# v1_0.net
KiCad netlist of a schematic drawn in EAGLE
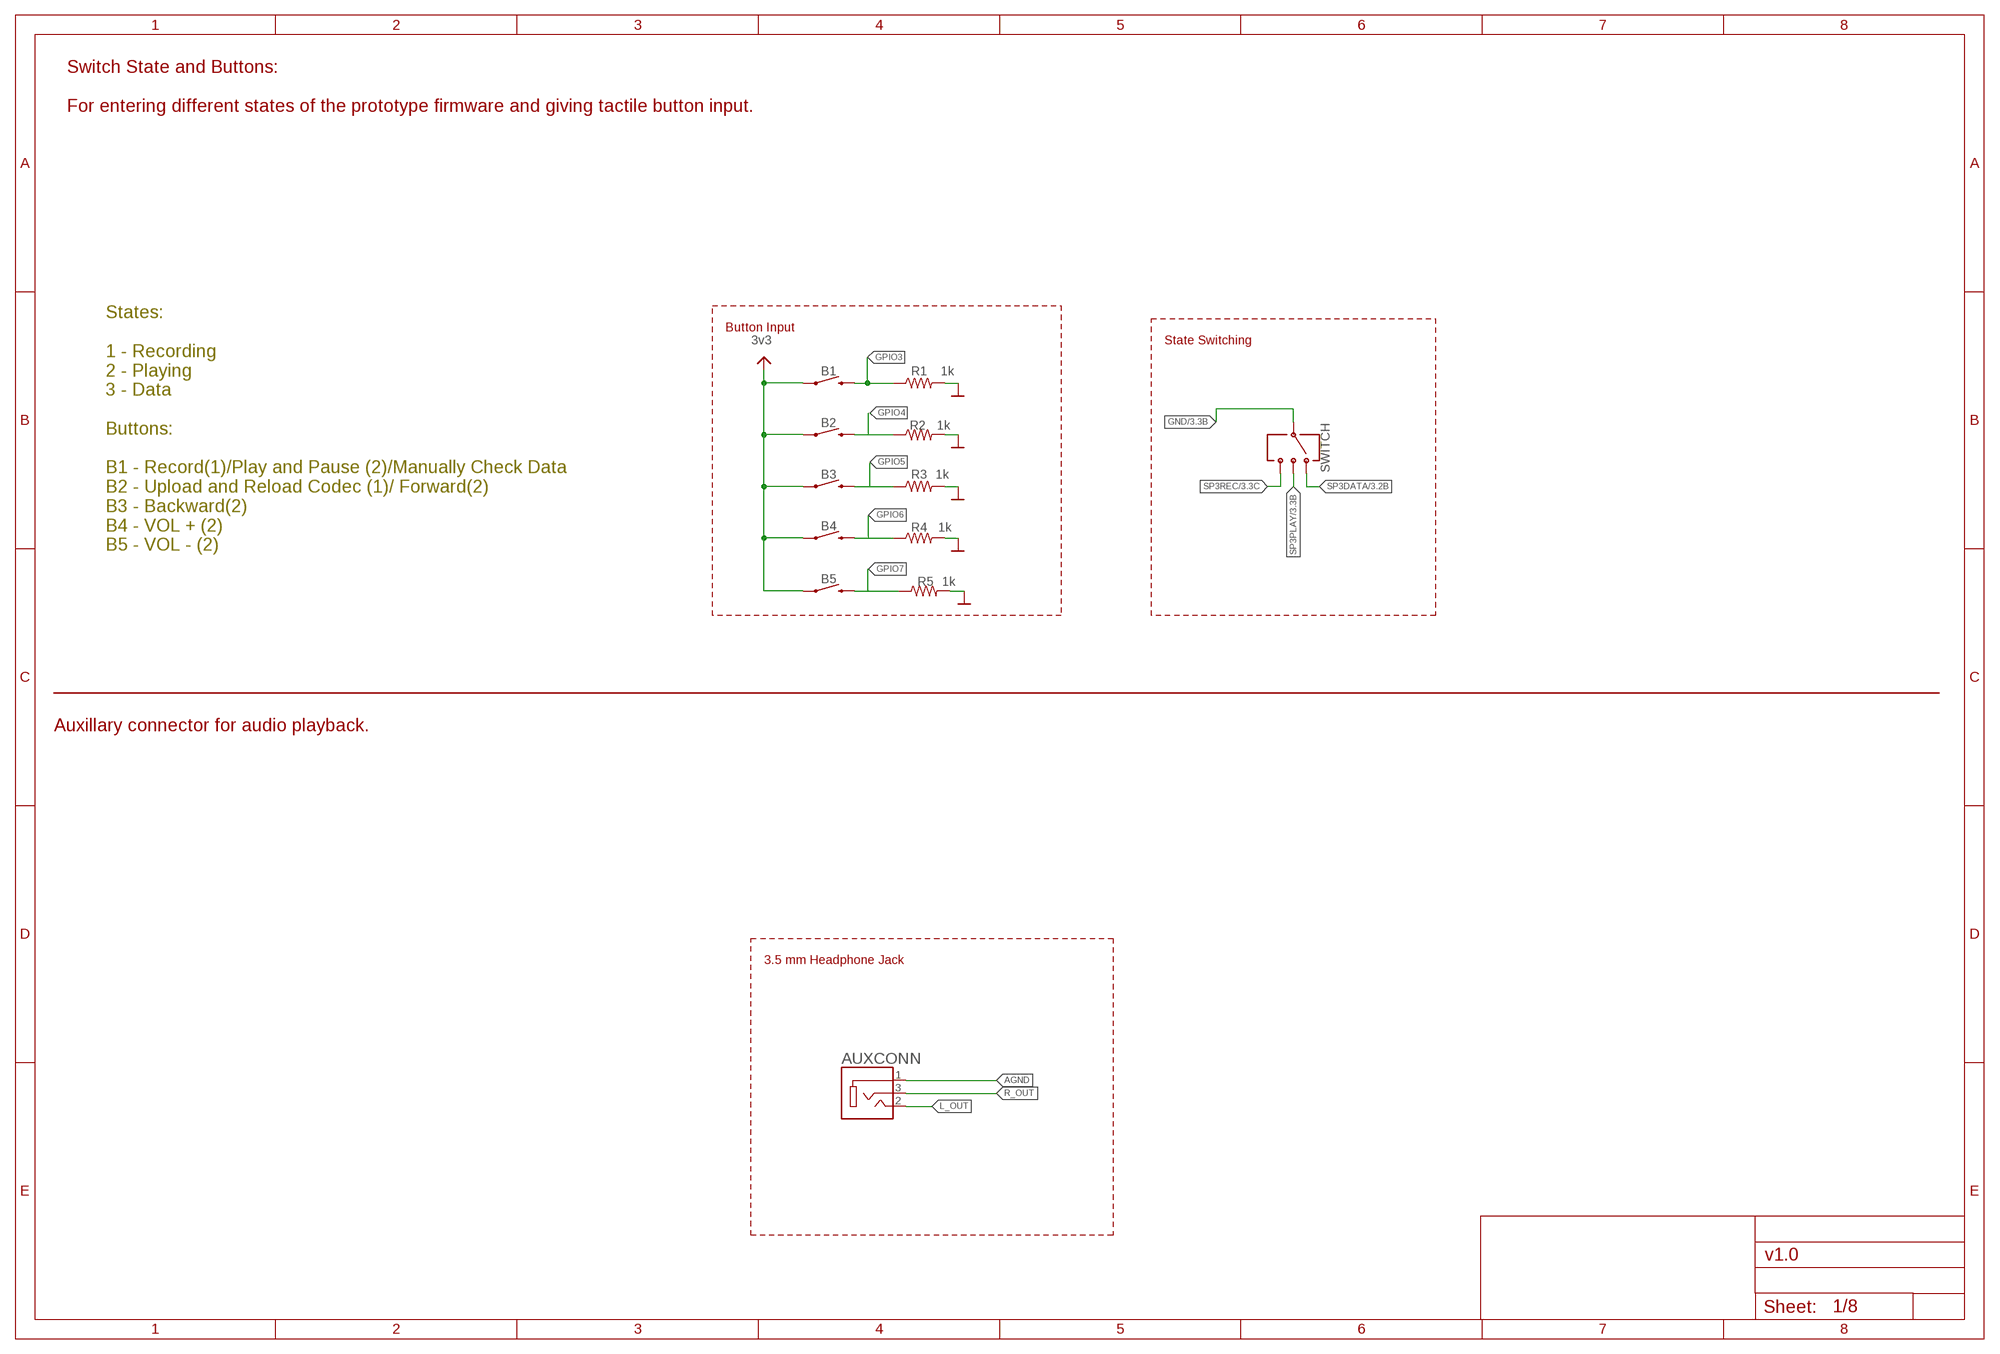
[diagram p0: schematic, sheet 1]
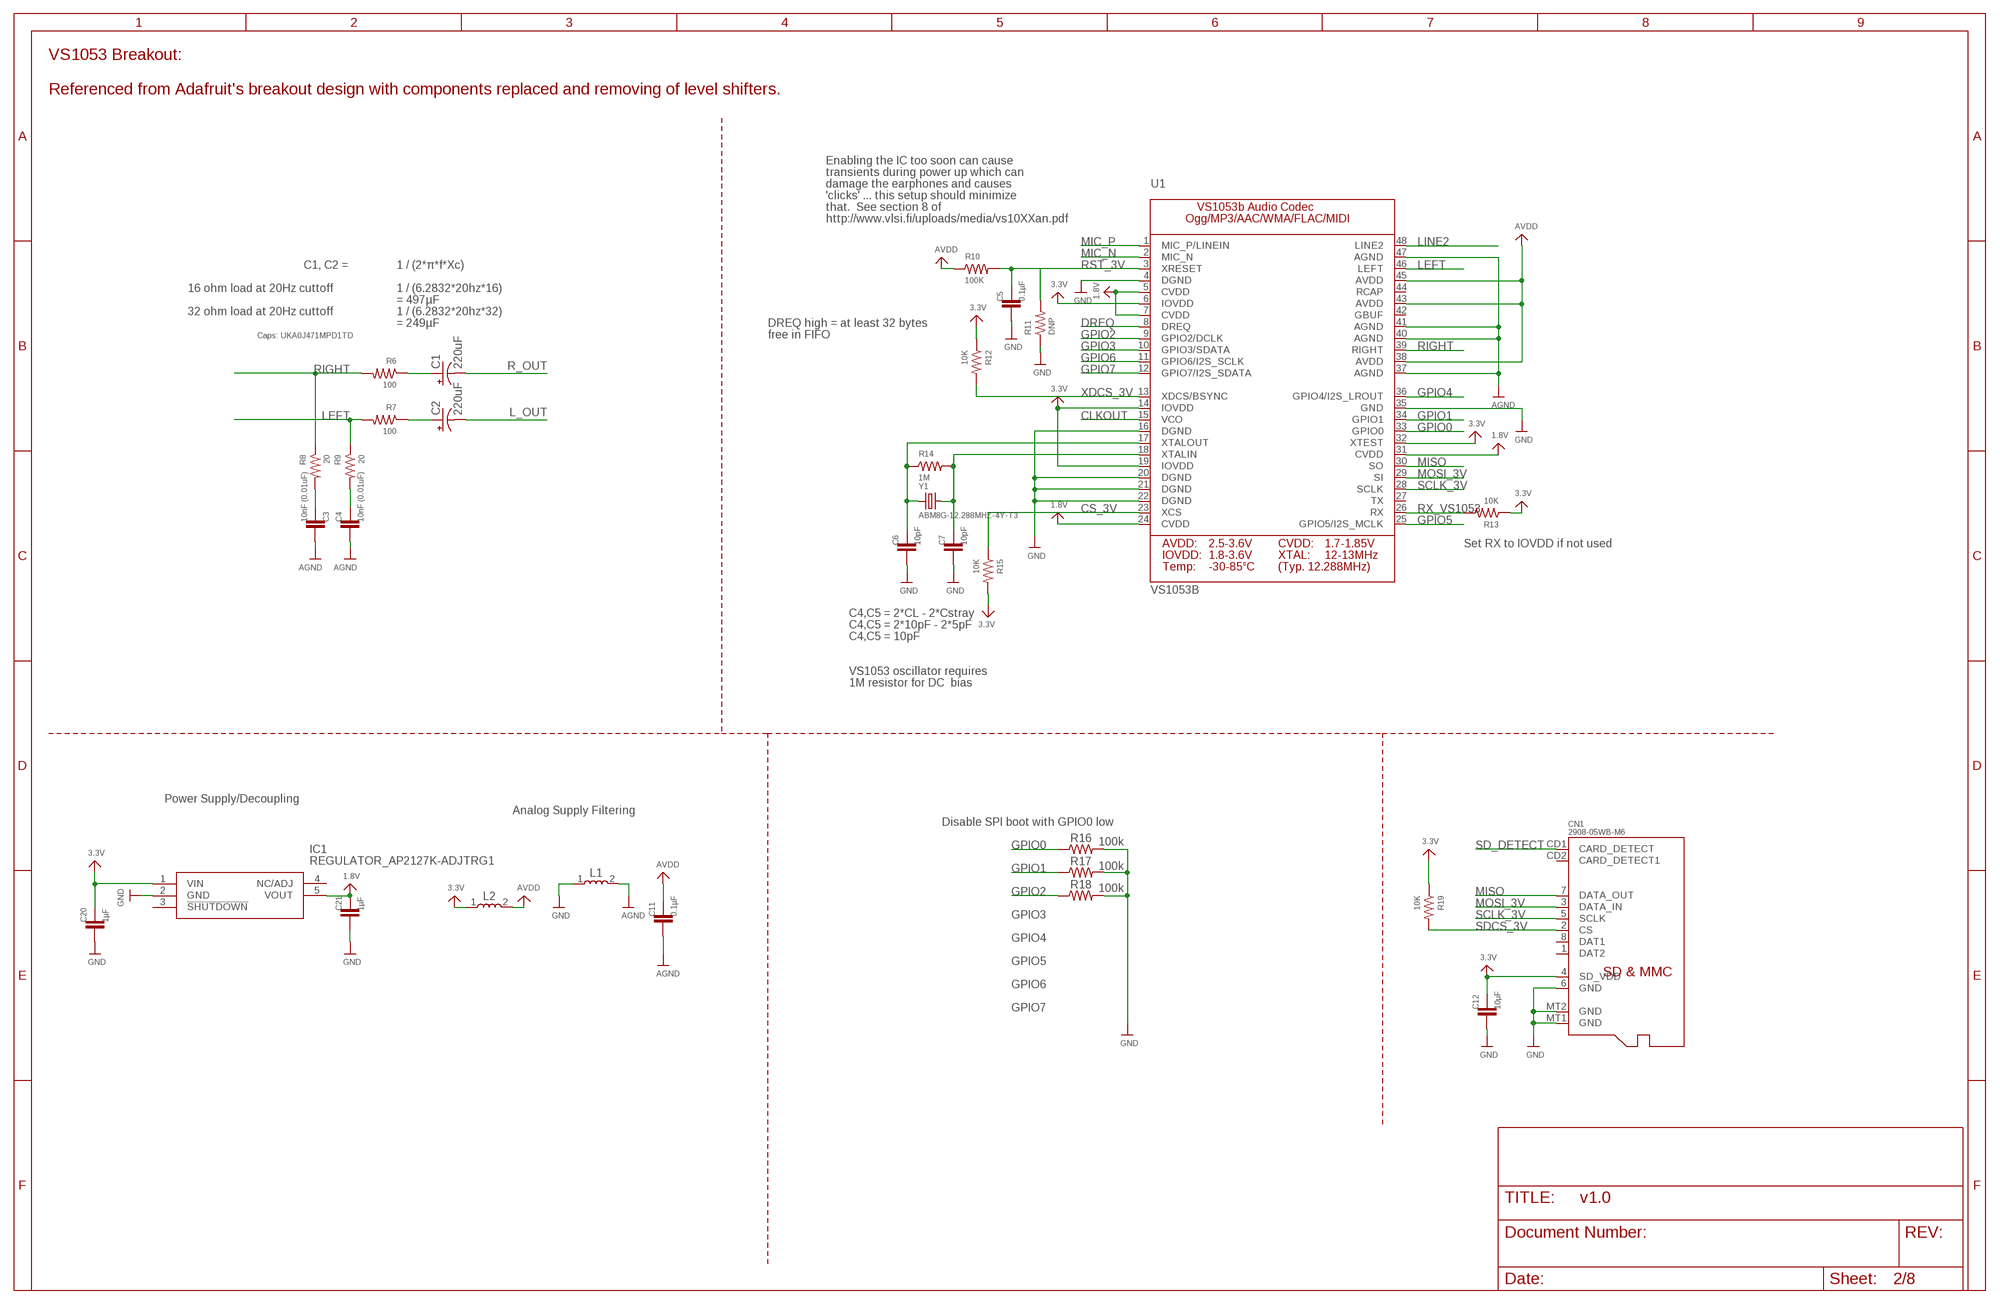
[diagram p1: schematic, sheet 2]
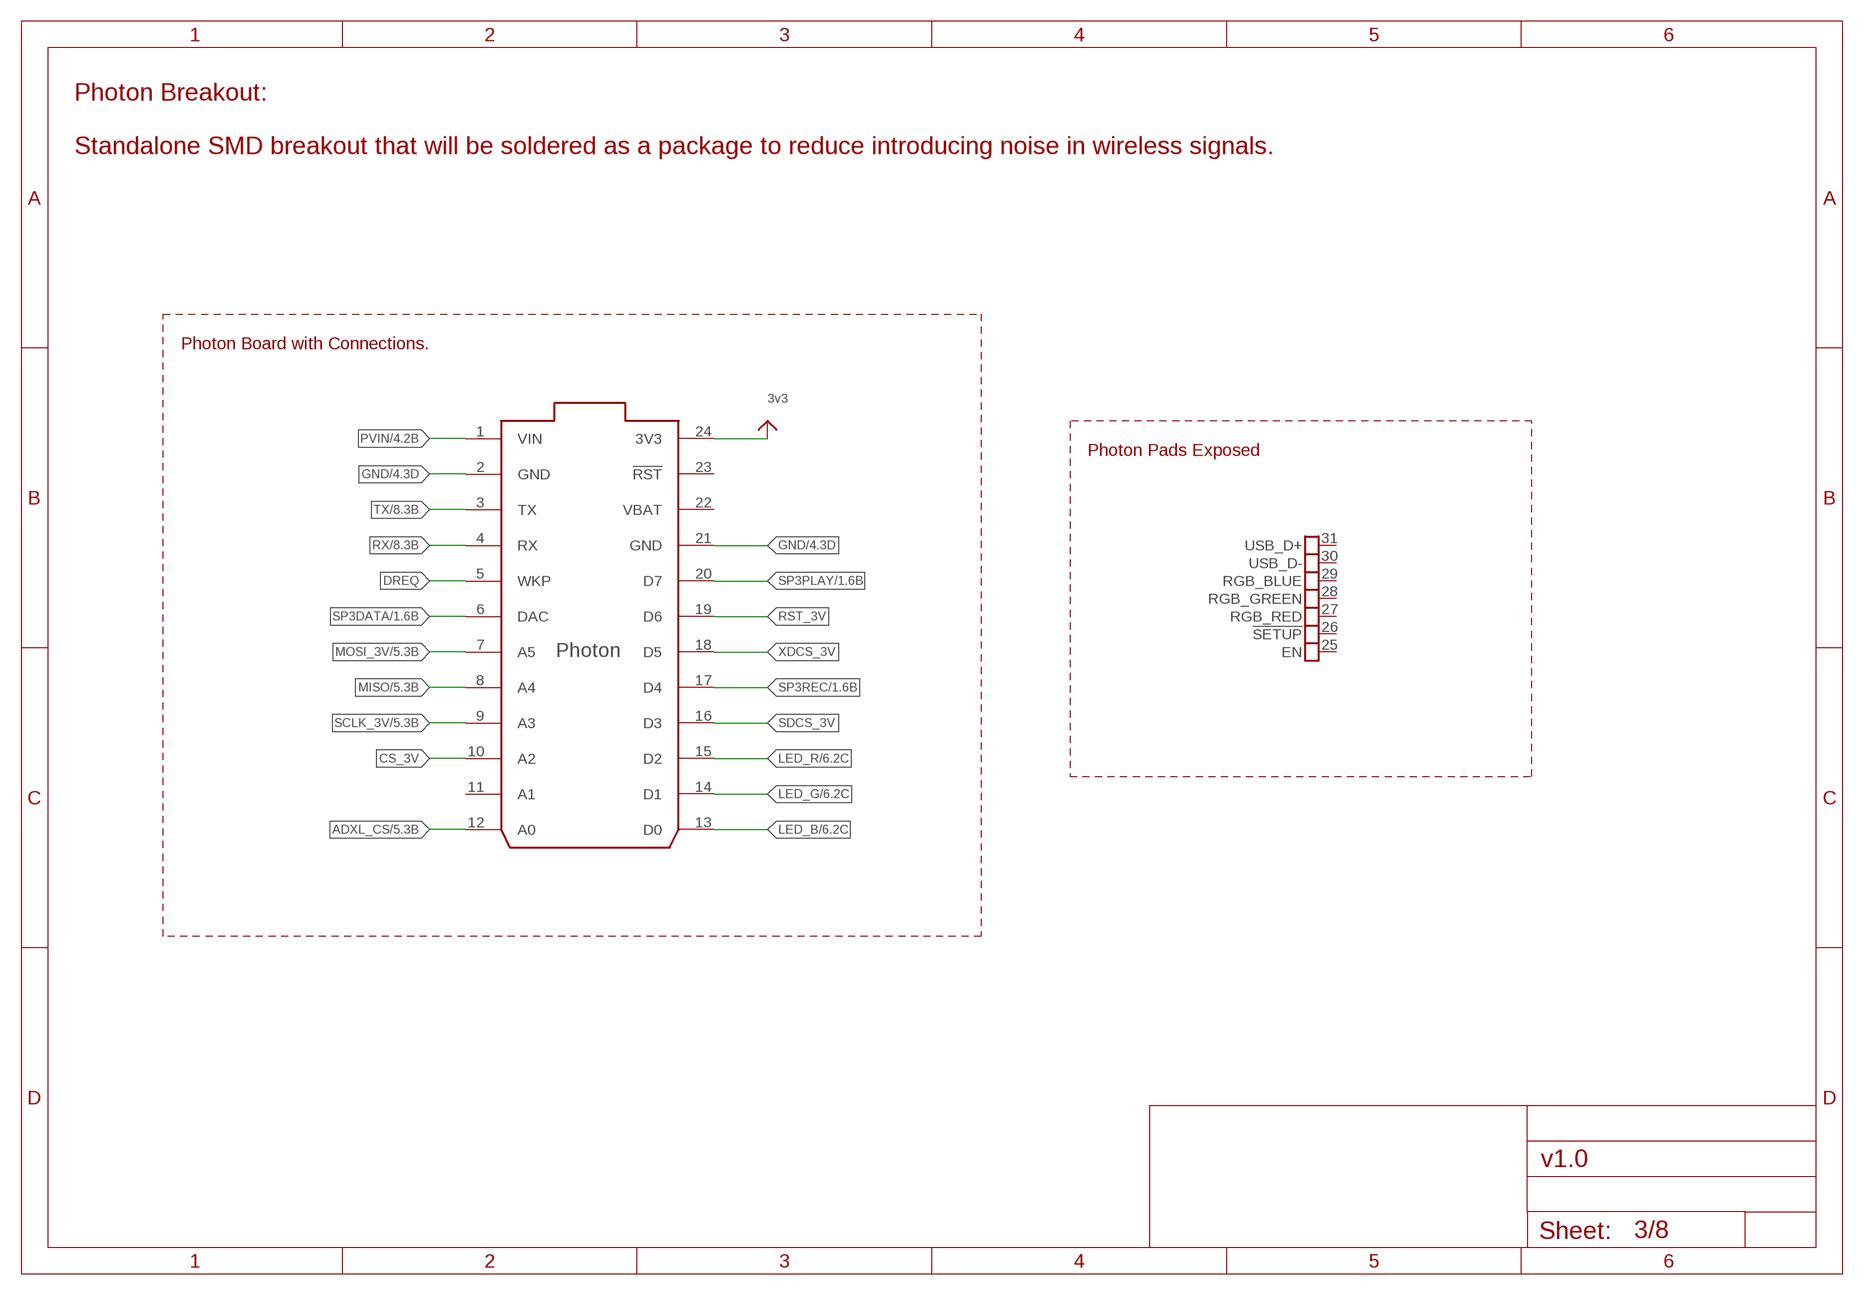
[diagram p2: schematic, sheet 3]
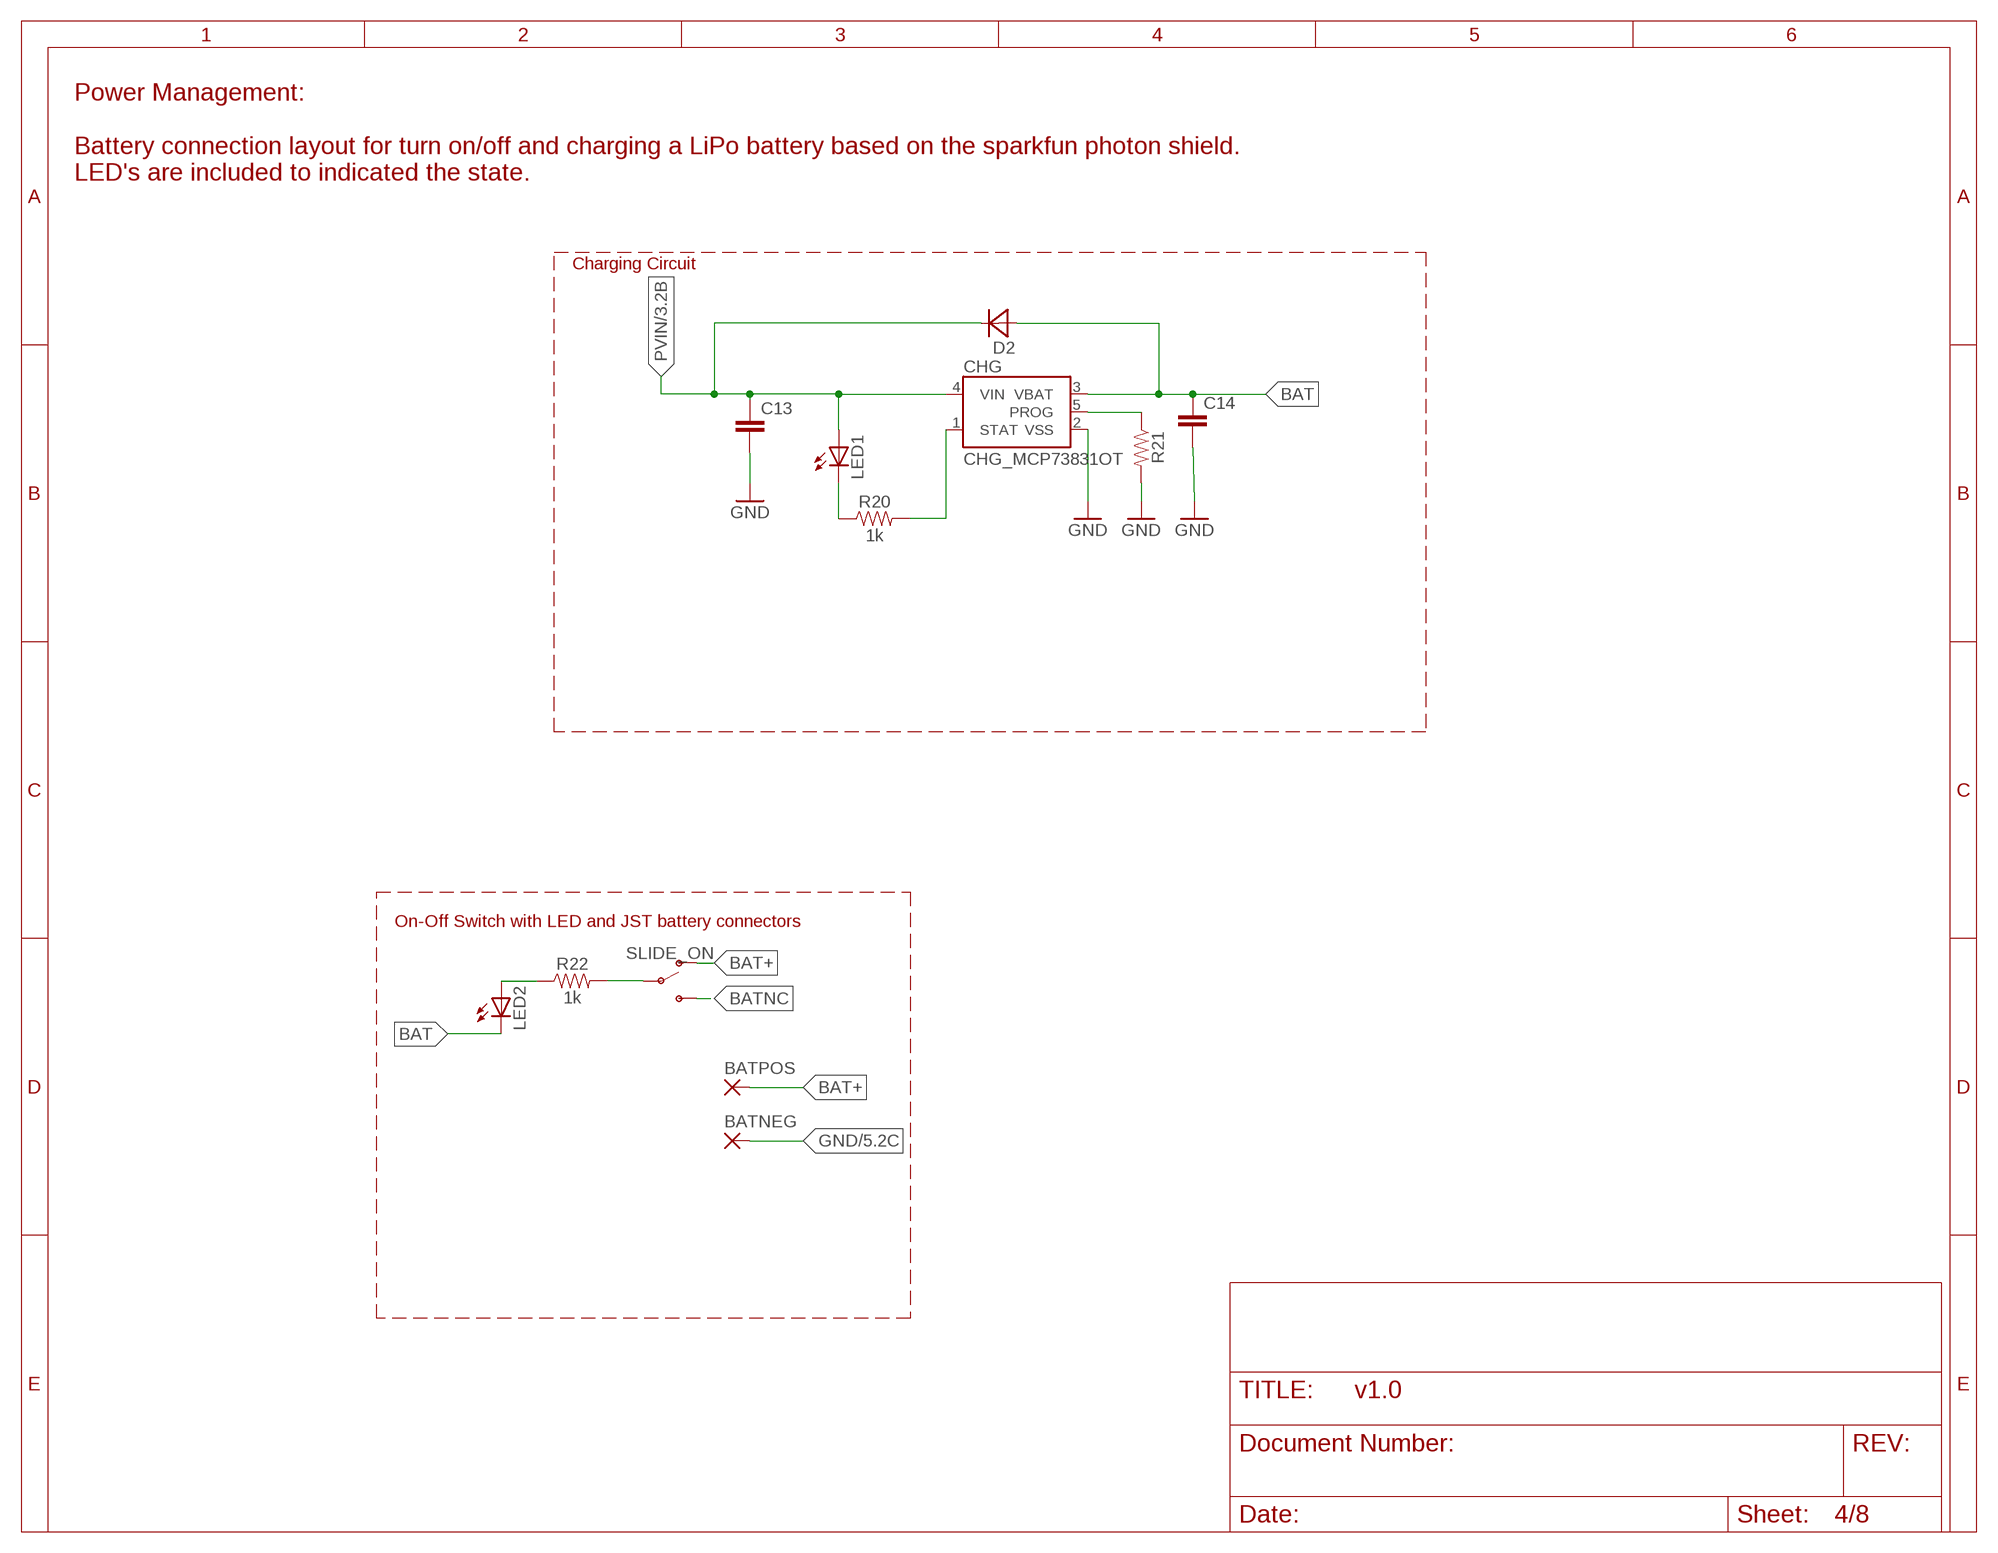
[diagram p3: schematic, sheet 4]
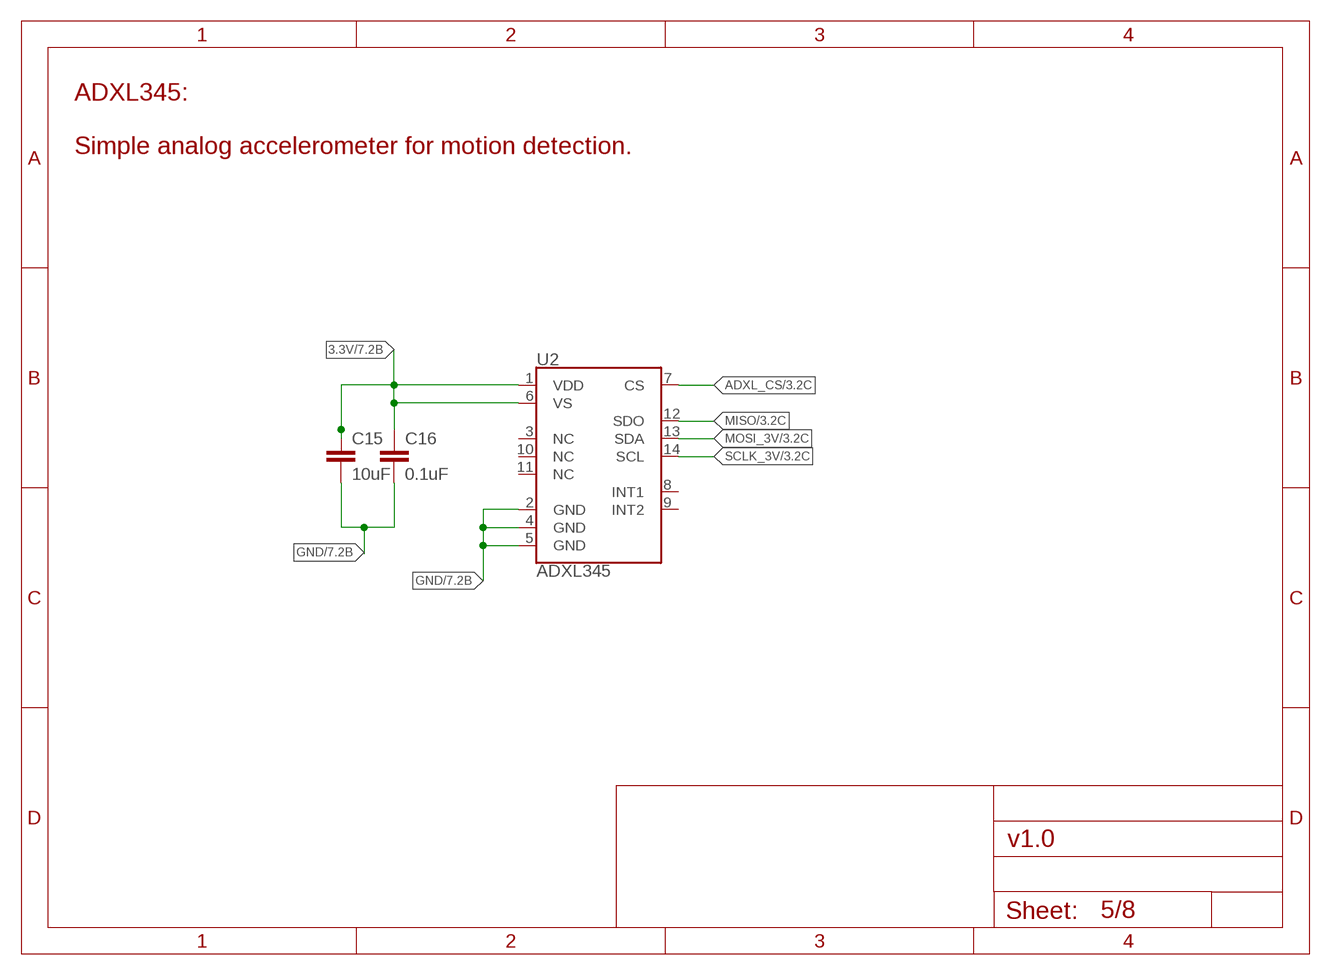
[diagram p4: schematic, sheet 5]
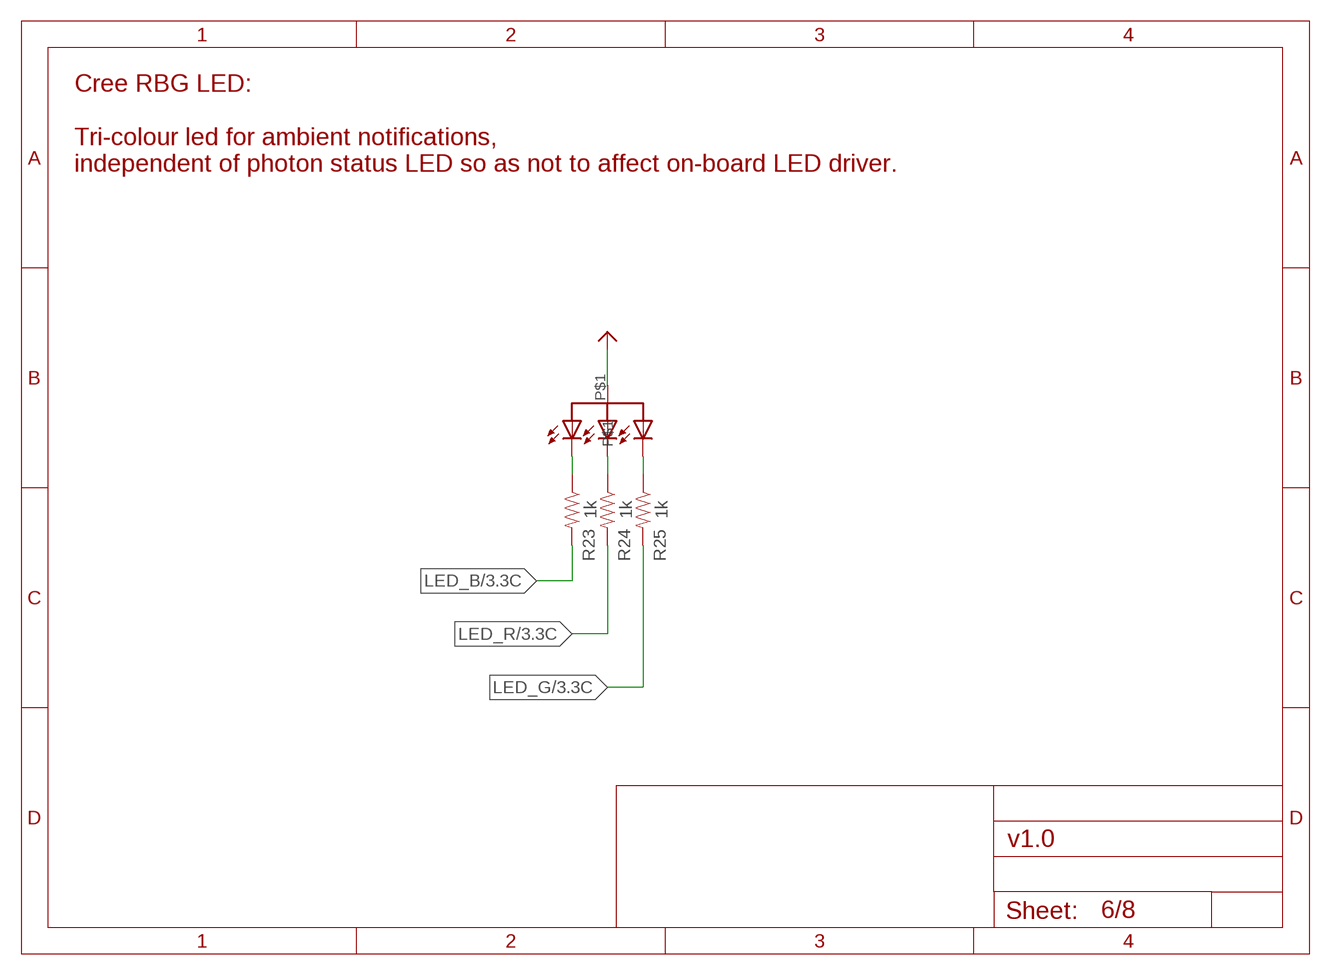
[diagram p5: schematic, sheet 6]
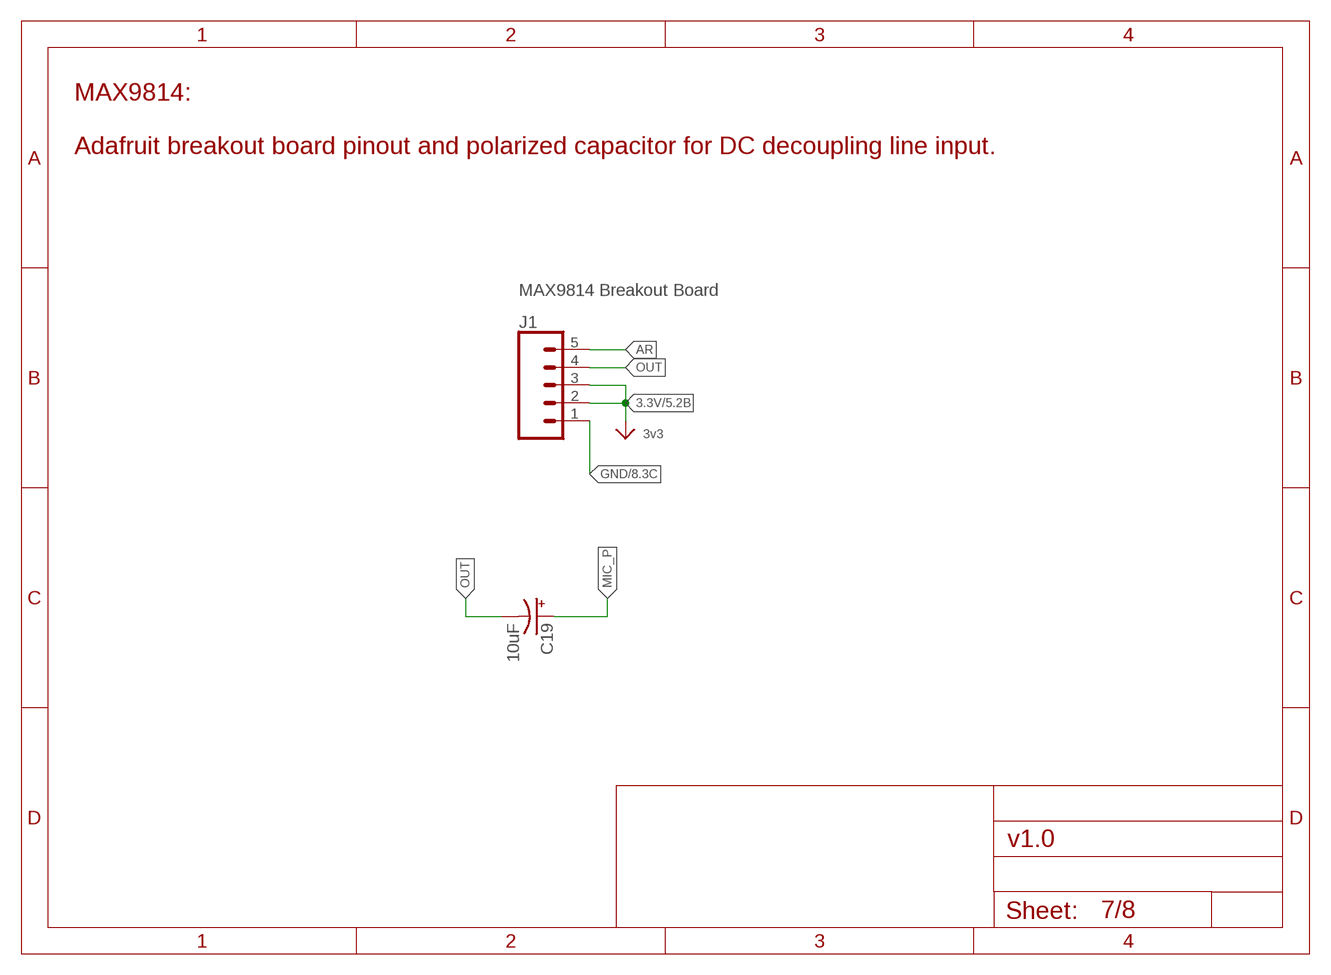
[diagram p6: schematic, sheet 7]
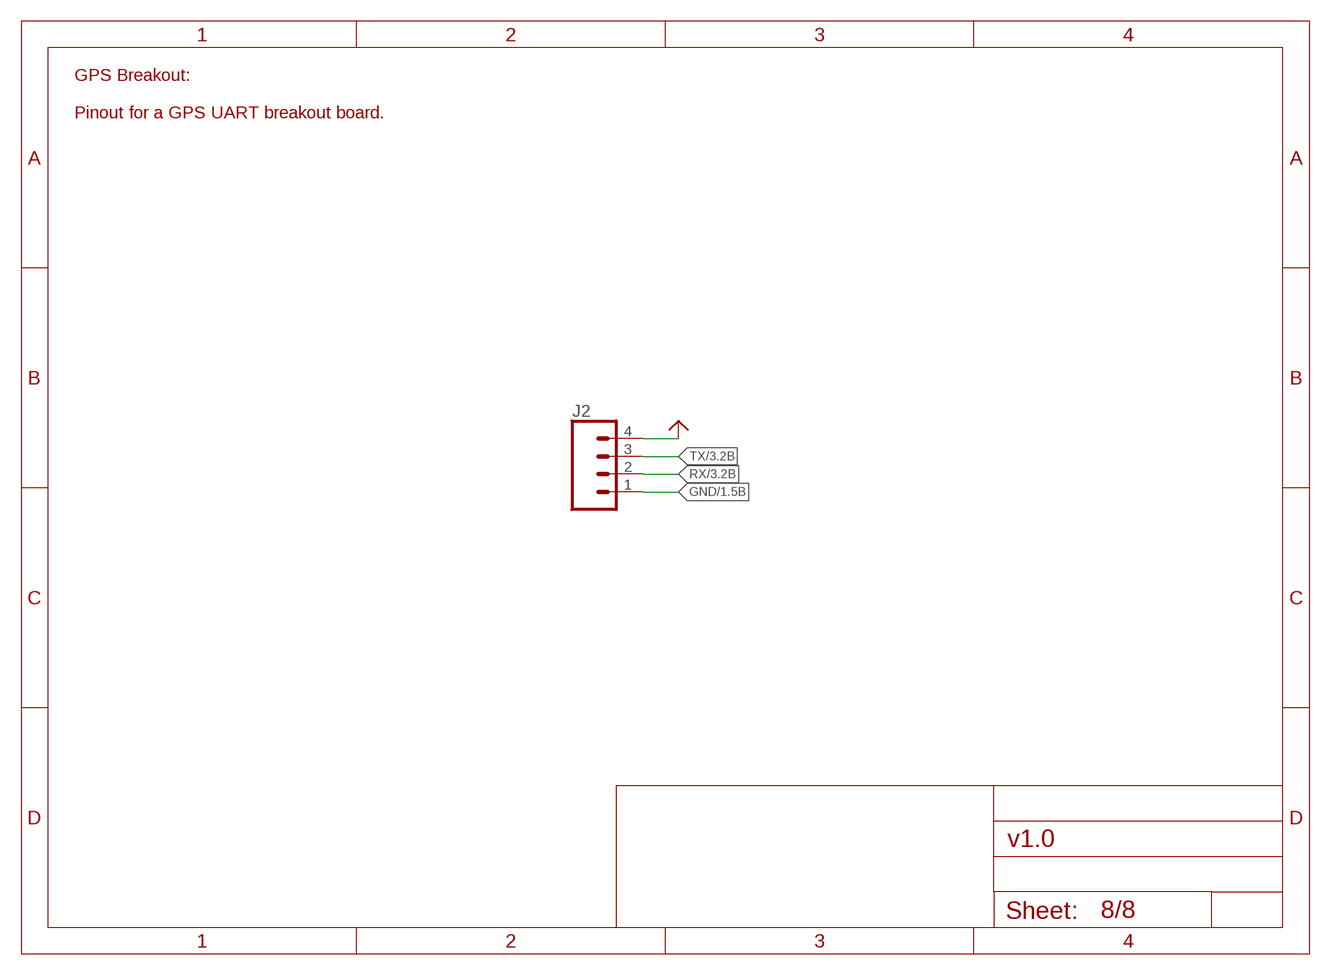
[diagram p7: schematic, sheet 8]

(export (version "E")
  (design (tool "Eeschema 10.0.6"))
  (components
    (comp (ref "J2")
      (value "CONNECTORS_CONN_04")
      (footprint "eagle-import:!_CONNECTORS_1X04")
      (libsource (lib "eagle-import") (part "CONNECTORS_CONN_04"))
    )
    (comp (ref "AUXCONN")
      (value "3.5MM_AUX_JACK")
      (footprint "eagle-import:!_SJ-3523-SMT-TR_CUI_SJ-3523-SMT-TR")
      (fields (field (name "MF") "CUI Inc.") (field (name "MP") "SJ-3523-SMT-TR"))
      (libsource (lib "eagle-import") (part "3.5MM_AUX_JACK"))
    )
    (comp (ref "B1")
      (value "MOMENTARY-SWITCH-SPST-SMD-6.2MM-TALL")
      (footprint "eagle-import:!_TACTILE_SWITCH_SMD_6.2MM_TALL")
      (libsource (lib "eagle-import") (part "MOMENTARY-SWITCH-SPST-SMD-6.2MM-TALL"))
    )
    (comp (ref "B2")
      (value "MOMENTARY-SWITCH-SPST-SMD-6.2MM-TALL")
      (footprint "eagle-import:!_TACTILE_SWITCH_SMD_6.2MM_TALL")
      (libsource (lib "eagle-import") (part "MOMENTARY-SWITCH-SPST-SMD-6.2MM-TALL"))
    )
    (comp (ref "B3")
      (value "MOMENTARY-SWITCH-SPST-SMD-6.2MM-TALL")
      (footprint "eagle-import:!_TACTILE_SWITCH_SMD_6.2MM_TALL")
      (libsource (lib "eagle-import") (part "MOMENTARY-SWITCH-SPST-SMD-6.2MM-TALL"))
    )
    (comp (ref "B4")
      (value "MOMENTARY-SWITCH-SPST-SMD-6.2MM-TALL")
      (footprint "eagle-import:!_TACTILE_SWITCH_SMD_6.2MM_TALL")
      (libsource (lib "eagle-import") (part "MOMENTARY-SWITCH-SPST-SMD-6.2MM-TALL"))
    )
    (comp (ref "B5")
      (value "MOMENTARY-SWITCH-SPST-SMD-6.2MM-TALL")
      (footprint "eagle-import:!_TACTILE_SWITCH_SMD_6.2MM_TALL")
      (libsource (lib "eagle-import") (part "MOMENTARY-SWITCH-SPST-SMD-6.2MM-TALL"))
    )
    (comp (ref "R1")
      (value "1k")
      (footprint "eagle-import:!_0603")
      (libsource (lib "eagle-import") (part "RESISTOR0603"))
    )
    (comp (ref "R2")
      (value "1k")
      (footprint "eagle-import:!_0603")
      (libsource (lib "eagle-import") (part "RESISTOR0603"))
    )
    (comp (ref "R3")
      (value "1k")
      (footprint "eagle-import:!_0603")
      (libsource (lib "eagle-import") (part "RESISTOR0603"))
    )
    (comp (ref "R4")
      (value "1k")
      (footprint "eagle-import:!_0603")
      (libsource (lib "eagle-import") (part "RESISTOR0603"))
    )
    (comp (ref "R5")
      (value "1k")
      (footprint "eagle-import:!_0603")
      (libsource (lib "eagle-import") (part "RESISTOR0603"))
    )
    (comp (ref "SWITCH")
      (value "SWITCH-SP3T-SMD")
      (footprint "eagle-import:!SWITCH_SP3T_SMD")
      (libsource (lib "eagle-import") (part "SWITCH-SP3T-SMD"))
    )
    (comp (ref "C19")
      (value "10uF")
      (footprint "eagle-import:!_PARTICLE_PC0603")
      (libsource (lib "eagle-import") (part "PARTICLE_TANT-CAP0603"))
    )
    (comp (ref "J1")
      (value "CONNECTORS_CONN_05")
      (footprint "eagle-import:!_CONNECTORS_1X05")
      (libsource (lib "eagle-import") (part "CONNECTORS_CONN_05"))
    )
    (comp (ref "LED3")
      (value "LED_TRICOLOR_3.2X2.8")
      (footprint "eagle-import:!_LED_3.2X2.8")
      (libsource (lib "eagle-import") (part "LED_TRICOLOR_3.2X2.8"))
    )
    (comp (ref "R23")
      (value "1k")
      (footprint "eagle-import:!_0603")
      (libsource (lib "eagle-import") (part "RESISTOR0603"))
    )
    (comp (ref "R24")
      (value "1k")
      (footprint "eagle-import:!_0603")
      (libsource (lib "eagle-import") (part "RESISTOR0603"))
    )
    (comp (ref "R25")
      (value "1k")
      (footprint "eagle-import:!_0603")
      (libsource (lib "eagle-import") (part "RESISTOR0603"))
    )
    (comp (ref "BATNEG")
      (value "SMD5")
      (footprint "eagle-import:SMD2,54-5,08")
      (libsource (lib "eagle-import") (part "SMD5"))
    )
    (comp (ref "BATPOS")
      (value "SMD5")
      (footprint "eagle-import:SMD2,54-5,08")
      (libsource (lib "eagle-import") (part "SMD5"))
    )
    (comp (ref "C13")
      (value "4.7uF")
      (footprint "eagle-import:!_0603")
      (libsource (lib "eagle-import") (part "CAPACITOR0603"))
    )
    (comp (ref "C14")
      (value "4.7uF")
      (footprint "eagle-import:!_0603")
      (libsource (lib "eagle-import") (part "CAPACITOR0603"))
    )
    (comp (ref "CHG")
      (value "CHG_MCP73831OT")
      (footprint "eagle-import:!_SOT23-5")
      (libsource (lib "eagle-import") (part "CHG_MCP73831OT"))
    )
    (comp (ref "D2")
      (value "DIODE_MBRA140T3")
      (footprint "eagle-import:!_DIODE_SMA")
      (libsource (lib "eagle-import") (part "DIODE_MBRA140T3"))
    )
    (comp (ref "LED1")
      (value "PASSIVE_LED")
      (footprint "eagle-import:!_LED_0603")
      (libsource (lib "eagle-import") (part "PASSIVE_LED"))
    )
    (comp (ref "LED2")
      (value "PASSIVE_LED")
      (footprint "eagle-import:!_LED_0603")
      (libsource (lib "eagle-import") (part "PASSIVE_LED"))
    )
    (comp (ref "R20")
      (value "1k")
      (footprint "eagle-import:!_0603")
      (libsource (lib "eagle-import") (part "RESISTOR0603"))
    )
    (comp (ref "R21")
      (value "10k")
      (footprint "eagle-import:!_0603")
      (libsource (lib "eagle-import") (part "RESISTOR0603"))
    )
    (comp (ref "R22")
      (value "1k")
      (footprint "eagle-import:!_0603")
      (libsource (lib "eagle-import") (part "RESISTOR0603"))
    )
    (comp (ref "SLIDE_ON")
      (value "PASSIVE_SLIDE_SWITCHES")
      (footprint "eagle-import:!_SWITCH_PCM12SMTR")
      (libsource (lib "eagle-import") (part "PASSIVE_SLIDE_SWITCHES"))
    )
    (comp (ref "C1")
      (value "220uF")
      (footprint "eagle-import:!_PANASONIC_E")
      (libsource (lib "eagle-import") (part "PANASONIC_CAPACITORE"))
    )
    (comp (ref "C2")
      (value "220uF")
      (footprint "eagle-import:!_PANASONIC_E")
      (libsource (lib "eagle-import") (part "PANASONIC_CAPACITORE"))
    )
    (comp (ref "C3")
      (value "10nF (0.01uF)")
      (footprint "eagle-import:!_0603")
      (libsource (lib "eagle-import") (part "CAPACITOR0603"))
    )
    (comp (ref "C4")
      (value "10nF (0.01uF)")
      (footprint "eagle-import:!_0603")
      (libsource (lib "eagle-import") (part "CAPACITOR0603"))
    )
    (comp (ref "C5")
      (value "0.1µF")
      (footprint "eagle-import:!_0603")
      (libsource (lib "eagle-import") (part "CAPACITOR0603"))
    )
    (comp (ref "C6")
      (value "10pF")
      (footprint "eagle-import:!_0603")
      (libsource (lib "eagle-import") (part "CAPACITOR0603"))
    )
    (comp (ref "C7")
      (value "10pF")
      (footprint "eagle-import:!_0603")
      (libsource (lib "eagle-import") (part "CAPACITOR0603"))
    )
    (comp (ref "C11")
      (value "0.1µF")
      (footprint "eagle-import:!_0603")
      (libsource (lib "eagle-import") (part "CAPACITOR0603"))
    )
    (comp (ref "C12")
      (value "10µF")
      (footprint "eagle-import:!_0603")
      (libsource (lib "eagle-import") (part "CAPACITOR0603"))
    )
    (comp (ref "C20")
      (value "1µF")
      (footprint "eagle-import:!_0603")
      (libsource (lib "eagle-import") (part "CAPACITOR0603"))
    )
    (comp (ref "C21")
      (value "1µF")
      (footprint "eagle-import:!_0603")
      (libsource (lib "eagle-import") (part "CAPACITOR0603"))
    )
    (comp (ref "CN1")
      (value "2908-05WB-M6")
      (footprint "eagle-import:!_MICROSD")
      (libsource (lib "eagle-import") (part "MICROSD_SPI"))
    )
    (comp (ref "IC1")
      (value "REGULATOR_AP2127K-ADJTRG1")
      (footprint "eagle-import:!_AP2127K-ADJTRG1_SOT95P282X145-5N")
      (fields
        (field (name "MANUFACTURER_PART_NUMBER") "AP2127K-ADJTRG1")
        (field (name "MOUSER_PART_NUMBER") "621-AP2127K-ADJTRG1")
        (field (name "RS_PART_NUMBER") "9210382P")
      )
      (libsource (lib "eagle-import") (part "REGULATOR_AP2127K-ADJTRG1"))
    )
    (comp (ref "L1")
      (value "FERRITE_BEAD0805")
      (footprint "eagle-import:!_FERRITE_0805")
      (libsource (lib "eagle-import") (part "FERRITE_BEAD0805"))
    )
    (comp (ref "L2")
      (value "FERRITE_BEAD0805")
      (footprint "eagle-import:!_FERRITE_0805")
      (libsource (lib "eagle-import") (part "FERRITE_BEAD0805"))
    )
    (comp (ref "R6")
      (value "100")
      (footprint "eagle-import:!_0603")
      (libsource (lib "eagle-import") (part "RESISTOR0603"))
    )
    (comp (ref "R7")
      (value "100")
      (footprint "eagle-import:!_0603")
      (libsource (lib "eagle-import") (part "RESISTOR0603"))
    )
    (comp (ref "R8")
      (value "20")
      (footprint "eagle-import:!_0603")
      (libsource (lib "eagle-import") (part "RESISTOR0603"))
    )
    (comp (ref "R9")
      (value "20")
      (footprint "eagle-import:!_0603")
      (libsource (lib "eagle-import") (part "RESISTOR0603"))
    )
    (comp (ref "R10")
      (value "100K")
      (footprint "eagle-import:!_0603")
      (libsource (lib "eagle-import") (part "RESISTOR0603"))
    )
    (comp (ref "R11")
      (value "DNP")
      (footprint "eagle-import:!_0603")
      (libsource (lib "eagle-import") (part "RESISTOR0603"))
    )
    (comp (ref "R12")
      (value "10K")
      (footprint "eagle-import:!_0603")
      (libsource (lib "eagle-import") (part "RESISTOR0603"))
    )
    (comp (ref "R13")
      (value "10K")
      (footprint "eagle-import:!_0603")
      (libsource (lib "eagle-import") (part "RESISTOR0603"))
    )
    (comp (ref "R14")
      (value "1M")
      (footprint "eagle-import:!_0603")
      (libsource (lib "eagle-import") (part "RESISTOR0603"))
    )
    (comp (ref "R15")
      (value "10K")
      (footprint "eagle-import:!_0603")
      (libsource (lib "eagle-import") (part "RESISTOR0603"))
    )
    (comp (ref "R16")
      (value "100k")
      (footprint "eagle-import:!_0603")
      (libsource (lib "eagle-import") (part "RESISTOR0603"))
    )
    (comp (ref "R17")
      (value "100k")
      (footprint "eagle-import:!_0603")
      (libsource (lib "eagle-import") (part "RESISTOR0603"))
    )
    (comp (ref "R18")
      (value "100k")
      (footprint "eagle-import:!_0603")
      (libsource (lib "eagle-import") (part "RESISTOR0603"))
    )
    (comp (ref "R19")
      (value "10K")
      (footprint "eagle-import:!_0603")
      (libsource (lib "eagle-import") (part "RESISTOR0603"))
    )
    (comp (ref "U1")
      (value "VS1053B")
      (footprint "eagle-import:!VS1053_LQFP48")
      (libsource (lib "eagle-import") (part "VS1053B"))
    )
    (comp (ref "Y1")
      (value "ABM8G-12.288MHZ-4Y-T3")
      (footprint "eagle-import:!_CRYSTAL_3.2X2.5")
      (libsource (lib "eagle-import") (part "MEMS_SMT_CRYSTAL3.2X2.5"))
    )
    (comp (ref "U$1")
      (value "PARTICLE-DEVICES_PHOTON_SMD")
      (footprint "eagle-import:!_PARTICLE-DEVICES_PHOTON_SMD")
      (libsource (lib "eagle-import") (part "PARTICLE-DEVICES_PHOTON_SMD"))
    )
    (comp (ref "C15")
      (value "10uF")
      (footprint "eagle-import:!_0603")
      (libsource (lib "eagle-import") (part "CAPACITOR0603"))
    )
    (comp (ref "C16")
      (value "0.1uF")
      (footprint "eagle-import:!_0603")
      (libsource (lib "eagle-import") (part "CAPACITOR0603"))
    )
    (comp (ref "U2")
      (value "ADXL345")
      (footprint "eagle-import:!_ADXL345_LGA-14")
      (fields (field (name "MF") "Analog Devices"))
      (libsource (lib "eagle-import") (part "ADXL345"))
    )
  )
  (nets
    (net (code "1") (name "1.8V") (class "Default")
      (node (ref "C21") (pin "1") (pinfunction "1_1") (pintype "passive"))
      (node (ref "IC1") (pin "5") (pinfunction "VOUT_5") (pintype "bidirectional"))
      (node (ref "U1") (pin "24") (pinfunction "CVDD_24") (pintype "power_in"))
      (node (ref "U1") (pin "31") (pinfunction "CVDD_31") (pintype "power_in"))
      (node (ref "U1") (pin "5") (pinfunction "CVDD_5") (pintype "power_in"))
      (node (ref "U1") (pin "7") (pinfunction "CVDD_7") (pintype "power_in"))
    )
    (net (code "2") (name "3.3V") (class "Default")
      (node (ref "B1") (pin "A2") (pinfunction "1_A2") (pintype "passive"))
      (node (ref "B2") (pin "A2") (pinfunction "1_A2") (pintype "passive"))
      (node (ref "B3") (pin "A2") (pinfunction "1_A2") (pintype "passive"))
      (node (ref "B4") (pin "A2") (pinfunction "1_A2") (pintype "passive"))
      (node (ref "B5") (pin "A2") (pinfunction "1_A2") (pintype "passive"))
      (node (ref "C12") (pin "1") (pinfunction "1_1") (pintype "passive"))
      (node (ref "C15") (pin "1") (pinfunction "1_1") (pintype "passive"))
      (node (ref "C16") (pin "1") (pinfunction "1_1") (pintype "passive"))
      (node (ref "C20") (pin "1") (pinfunction "1_1") (pintype "passive"))
      (node (ref "CN1") (pin "4") (pinfunction "SD_VDD_4") (pintype "power_in"))
      (node (ref "IC1") (pin "1") (pinfunction "VIN_1") (pintype "bidirectional"))
      (node (ref "J1") (pin "2") (pinfunction "2_2") (pintype "passive"))
      (node (ref "J1") (pin "3") (pinfunction "3_3") (pintype "passive"))
      (node (ref "J2") (pin "4") (pinfunction "4_4") (pintype "passive"))
      (node (ref "L2") (pin "1") (pinfunction "1_1") (pintype "passive"))
      (node (ref "LED3") (pin "P$1") (pinfunction "P$1_P$1") (pintype "input"))
      (node (ref "R12") (pin "1") (pinfunction "1_1") (pintype "passive"))
      (node (ref "R13") (pin "1") (pinfunction "1_1") (pintype "passive"))
      (node (ref "R15") (pin "2") (pinfunction "2_2") (pintype "passive"))
      (node (ref "R19") (pin "1") (pinfunction "1_1") (pintype "passive"))
      (node (ref "U$1") (pin "24") (pinfunction "3V3_24") (pintype "power_in"))
      (node (ref "U1") (pin "14") (pinfunction "IOVDD_14") (pintype "power_in"))
      (node (ref "U1") (pin "19") (pinfunction "IOVDD_19") (pintype "power_in"))
      (node (ref "U1") (pin "32") (pinfunction "XTEST_32") (pintype "bidirectional"))
      (node (ref "U1") (pin "6") (pinfunction "IOVDD_6") (pintype "power_in"))
      (node (ref "U2") (pin "1") (pinfunction "VDD_1") (pintype "bidirectional"))
      (node (ref "U2") (pin "6") (pinfunction "VS_6") (pintype "bidirectional"))
    )
    (net (code "3") (name "ADXL_CS") (class "Default")
      (node (ref "U$1") (pin "12") (pinfunction "A0_12") (pintype "bidirectional"))
      (node (ref "U2") (pin "7") (pinfunction "CS_7") (pintype "bidirectional"))
    )
    (net (code "4") (name "AGND") (class "Default")
      (node (ref "AUXCONN") (pin "1") (pinfunction "1_1") (pintype "passive"))
      (node (ref "C11") (pin "2") (pinfunction "2_2") (pintype "passive"))
      (node (ref "C3") (pin "2") (pinfunction "2_2") (pintype "passive"))
      (node (ref "C4") (pin "2") (pinfunction "2_2") (pintype "passive"))
      (node (ref "L1") (pin "2") (pinfunction "2_2") (pintype "passive"))
      (node (ref "U1") (pin "37") (pinfunction "AGND_37") (pintype "power_in"))
      (node (ref "U1") (pin "40") (pinfunction "AGND_40") (pintype "power_in"))
      (node (ref "U1") (pin "41") (pinfunction "AGND_41") (pintype "power_in"))
      (node (ref "U1") (pin "47") (pinfunction "AGND_47") (pintype "power_in"))
    )
    (net (code "5") (name "AR") (class "Default")
      (node (ref "J1") (pin "5") (pinfunction "5_5") (pintype "passive"))
    )
    (net (code "6") (name "AVDD") (class "Default")
      (node (ref "C11") (pin "1") (pinfunction "1_1") (pintype "passive"))
      (node (ref "L2") (pin "2") (pinfunction "2_2") (pintype "passive"))
      (node (ref "R10") (pin "1") (pinfunction "1_1") (pintype "passive"))
      (node (ref "U1") (pin "38") (pinfunction "AVDD_38") (pintype "power_in"))
      (node (ref "U1") (pin "43") (pinfunction "AVDD_43") (pintype "power_in"))
      (node (ref "U1") (pin "45") (pinfunction "AVDD_45") (pintype "power_in"))
    )
    (net (code "7") (name "BAT") (class "Default")
      (node (ref "C14") (pin "1") (pinfunction "1_1") (pintype "passive"))
      (node (ref "CHG") (pin "3") (pinfunction "VBAT_3") (pintype "power_in"))
      (node (ref "D2") (pin "A") (pinfunction "A_A") (pintype "passive"))
      (node (ref "LED2") (pin "C") (pinfunction "C_C") (pintype "passive"))
    )
    (net (code "8") (name "BAT+") (class "Default")
      (node (ref "BATPOS") (pin "1") (pinfunction "P_1") (pintype "passive"))
      (node (ref "SLIDE_ON") (pin "O") (pinfunction "O_O") (pintype "passive"))
    )
    (net (code "9") (name "BATNC") (class "Default")
      (node (ref "SLIDE_ON") (pin "S") (pinfunction "S_S") (pintype "passive"))
    )
    (net (code "10") (name "CLKOUT") (class "Default")
      (node (ref "U1") (pin "15") (pinfunction "VCO_15") (pintype "bidirectional"))
    )
    (net (code "11") (name "CS_3V") (class "Default")
      (node (ref "R15") (pin "1") (pinfunction "1_1") (pintype "passive"))
      (node (ref "U$1") (pin "10") (pinfunction "A2_10") (pintype "bidirectional"))
      (node (ref "U1") (pin "23") (pinfunction "XCS_23") (pintype "bidirectional"))
    )
    (net (code "12") (name "DREQ") (class "Default")
      (node (ref "U$1") (pin "5") (pinfunction "WKP_5") (pintype "bidirectional"))
      (node (ref "U1") (pin "8") (pinfunction "DREQ_8") (pintype "bidirectional"))
    )
    (net (code "13") (name "GND") (class "Default")
      (node (ref "BATNEG") (pin "1") (pinfunction "P_1") (pintype "passive"))
      (node (ref "C12") (pin "2") (pinfunction "2_2") (pintype "passive"))
      (node (ref "C13") (pin "2") (pinfunction "2_2") (pintype "passive"))
      (node (ref "C14") (pin "2") (pinfunction "2_2") (pintype "passive"))
      (node (ref "C15") (pin "2") (pinfunction "2_2") (pintype "passive"))
      (node (ref "C16") (pin "2") (pinfunction "2_2") (pintype "passive"))
      (node (ref "C20") (pin "2") (pinfunction "2_2") (pintype "passive"))
      (node (ref "C21") (pin "2") (pinfunction "2_2") (pintype "passive"))
      (node (ref "C5") (pin "2") (pinfunction "2_2") (pintype "passive"))
      (node (ref "C6") (pin "2") (pinfunction "2_2") (pintype "passive"))
      (node (ref "C7") (pin "2") (pinfunction "2_2") (pintype "passive"))
      (node (ref "CHG") (pin "2") (pinfunction "VSS_2") (pintype "power_in"))
      (node (ref "CN1") (pin "6") (pinfunction "GND_6") (pintype "power_in"))
      (node (ref "CN1") (pin "MT1") (pinfunction "GND_MT1") (pintype "power_in"))
      (node (ref "CN1") (pin "MT2") (pinfunction "GND_MT2") (pintype "power_in"))
      (node (ref "IC1") (pin "2") (pinfunction "GND_2") (pintype "bidirectional"))
      (node (ref "J1") (pin "1") (pinfunction "1_1") (pintype "passive"))
      (node (ref "J2") (pin "1") (pinfunction "1_1") (pintype "passive"))
      (node (ref "L1") (pin "1") (pinfunction "1_1") (pintype "passive"))
      (node (ref "R1") (pin "2") (pinfunction "2_2") (pintype "passive"))
      (node (ref "R11") (pin "1") (pinfunction "1_1") (pintype "passive"))
      (node (ref "R16") (pin "2") (pinfunction "2_2") (pintype "passive"))
      (node (ref "R17") (pin "2") (pinfunction "2_2") (pintype "passive"))
      (node (ref "R18") (pin "2") (pinfunction "2_2") (pintype "passive"))
      (node (ref "R2") (pin "2") (pinfunction "2_2") (pintype "passive"))
      (node (ref "R21") (pin "2") (pinfunction "2_2") (pintype "passive"))
      (node (ref "R3") (pin "2") (pinfunction "2_2") (pintype "passive"))
      (node (ref "R4") (pin "2") (pinfunction "2_2") (pintype "passive"))
      (node (ref "R5") (pin "2") (pinfunction "2_2") (pintype "passive"))
      (node (ref "SWITCH") (pin "3") (pinfunction "3_3") (pintype "bidirectional"))
      (node (ref "U$1") (pin "2") (pinfunction "GND_2") (pintype "power_in"))
      (node (ref "U$1") (pin "21") (pinfunction "GND_21") (pintype "power_in"))
      (node (ref "U1") (pin "16") (pinfunction "DGND_16") (pintype "power_in"))
      (node (ref "U1") (pin "20") (pinfunction "DGND_20") (pintype "power_in"))
      (node (ref "U1") (pin "21") (pinfunction "DGND_21") (pintype "power_in"))
      (node (ref "U1") (pin "22") (pinfunction "DGND_22") (pintype "power_in"))
      (node (ref "U1") (pin "35") (pinfunction "GND_35") (pintype "power_in"))
      (node (ref "U1") (pin "4") (pinfunction "DGND_4") (pintype "power_in"))
      (node (ref "U2") (pin "2") (pinfunction "GND_2") (pintype "bidirectional"))
      (node (ref "U2") (pin "4") (pinfunction "GND_4") (pintype "bidirectional"))
      (node (ref "U2") (pin "5") (pinfunction "GND_5") (pintype "bidirectional"))
    )
    (net (code "14") (name "GPIO0") (class "Default")
      (node (ref "R16") (pin "1") (pinfunction "1_1") (pintype "passive"))
      (node (ref "U1") (pin "33") (pinfunction "GPIO0_33") (pintype "bidirectional"))
    )
    (net (code "15") (name "GPIO1") (class "Default")
      (node (ref "R17") (pin "1") (pinfunction "1_1") (pintype "passive"))
      (node (ref "U1") (pin "34") (pinfunction "GPIO1_34") (pintype "bidirectional"))
    )
    (net (code "16") (name "GPIO2") (class "Default")
      (node (ref "R18") (pin "1") (pinfunction "1_1") (pintype "passive"))
      (node (ref "U1") (pin "9") (pinfunction "GPIO2/DCLK_9") (pintype "bidirectional"))
    )
    (net (code "17") (name "GPIO3") (class "Default")
      (node (ref "B1") (pin "B2") (pinfunction "2_B2") (pintype "passive"))
      (node (ref "R1") (pin "1") (pinfunction "1_1") (pintype "passive"))
      (node (ref "U1") (pin "10") (pinfunction "GPIO3/SDATA_10") (pintype "bidirectional"))
    )
    (net (code "18") (name "GPIO4") (class "Default")
      (node (ref "B2") (pin "B2") (pinfunction "2_B2") (pintype "passive"))
      (node (ref "R2") (pin "1") (pinfunction "1_1") (pintype "passive"))
      (node (ref "U1") (pin "36") (pinfunction "GPIO4/I2S_LROUT_36") (pintype "bidirectional"))
    )
    (net (code "19") (name "GPIO5") (class "Default")
      (node (ref "B3") (pin "B2") (pinfunction "2_B2") (pintype "passive"))
      (node (ref "R3") (pin "1") (pinfunction "1_1") (pintype "passive"))
      (node (ref "U1") (pin "25") (pinfunction "GPIO5/I2S_MCLK_25") (pintype "bidirectional"))
    )
    (net (code "20") (name "GPIO6") (class "Default")
      (node (ref "B4") (pin "B2") (pinfunction "2_B2") (pintype "passive"))
      (node (ref "R4") (pin "1") (pinfunction "1_1") (pintype "passive"))
      (node (ref "U1") (pin "11") (pinfunction "GPIO6/I2S_SCLK_11") (pintype "bidirectional"))
    )
    (net (code "21") (name "GPIO7") (class "Default")
      (node (ref "B5") (pin "B2") (pinfunction "2_B2") (pintype "passive"))
      (node (ref "R5") (pin "1") (pinfunction "1_1") (pintype "passive"))
      (node (ref "U1") (pin "12") (pinfunction "GPIO7/I2S_SDATA_12") (pintype "bidirectional"))
    )
    (net (code "22") (name "LED_B") (class "Default")
      (node (ref "R23") (pin "2") (pinfunction "2_2") (pintype "passive"))
      (node (ref "U$1") (pin "13") (pinfunction "D0_13") (pintype "bidirectional"))
    )
    (net (code "23") (name "LED_G") (class "Default")
      (node (ref "R25") (pin "2") (pinfunction "2_2") (pintype "passive"))
      (node (ref "U$1") (pin "14") (pinfunction "D1_14") (pintype "bidirectional"))
    )
    (net (code "24") (name "LED_R") (class "Default")
      (node (ref "R24") (pin "2") (pinfunction "2_2") (pintype "passive"))
      (node (ref "U$1") (pin "15") (pinfunction "D2_15") (pintype "bidirectional"))
    )
    (net (code "25") (name "LEFT") (class "Default")
      (node (ref "R7") (pin "2") (pinfunction "2_2") (pintype "passive"))
      (node (ref "R9") (pin "1") (pinfunction "1_1") (pintype "passive"))
      (node (ref "U1") (pin "46") (pinfunction "LEFT_46") (pintype "bidirectional"))
    )
    (net (code "26") (name "LINE2") (class "Default")
      (node (ref "U1") (pin "48") (pinfunction "LINE2_48") (pintype "bidirectional"))
    )
    (net (code "27") (name "L_OUT") (class "Default")
      (node (ref "AUXCONN") (pin "2") (pinfunction "2_2") (pintype "passive"))
      (node (ref "C2") (pin "-") (pinfunction "-_-") (pintype "passive"))
    )
    (net (code "28") (name "MIC_N") (class "Default")
      (node (ref "U1") (pin "2") (pinfunction "MIC_N_2") (pintype "bidirectional"))
    )
    (net (code "29") (name "MIC_P") (class "Default")
      (node (ref "C19") (pin "A") (pinfunction "+_A") (pintype "passive"))
      (node (ref "U1") (pin "1") (pinfunction "MIC_P/LINEIN_1") (pintype "bidirectional"))
    )
    (net (code "30") (name "MISO") (class "Default")
      (node (ref "CN1") (pin "7") (pinfunction "DATA_OUT_7") (pintype "output"))
      (node (ref "U$1") (pin "8") (pinfunction "A4_8") (pintype "bidirectional"))
      (node (ref "U1") (pin "30") (pinfunction "SO_30") (pintype "bidirectional"))
      (node (ref "U2") (pin "12") (pinfunction "SDO_12") (pintype "bidirectional"))
    )
    (net (code "31") (name "MOSI_3V") (class "Default")
      (node (ref "CN1") (pin "3") (pinfunction "DATA_IN_3") (pintype "input"))
      (node (ref "U$1") (pin "7") (pinfunction "A5_7") (pintype "bidirectional"))
      (node (ref "U1") (pin "29") (pinfunction "SI_29") (pintype "bidirectional"))
      (node (ref "U2") (pin "13") (pinfunction "SDA_13") (pintype "bidirectional"))
    )
    (net (code "32") (name "Net-(C1-Pad+)") (class "Default")
      (node (ref "C1") (pin "+") (pinfunction "+_+") (pintype "passive"))
      (node (ref "R6") (pin "1") (pinfunction "1_1") (pintype "passive"))
    )
    (net (code "33") (name "Net-(C2-Pad+)") (class "Default")
      (node (ref "C2") (pin "+") (pinfunction "+_+") (pintype "passive"))
      (node (ref "R7") (pin "1") (pinfunction "1_1") (pintype "passive"))
    )
    (net (code "34") (name "Net-(C3-Pad1)") (class "Default")
      (node (ref "C3") (pin "1") (pinfunction "1_1") (pintype "passive"))
      (node (ref "R8") (pin "2") (pinfunction "2_2") (pintype "passive"))
    )
    (net (code "35") (name "Net-(C4-Pad1)") (class "Default")
      (node (ref "C4") (pin "1") (pinfunction "1_1") (pintype "passive"))
      (node (ref "R9") (pin "2") (pinfunction "2_2") (pintype "passive"))
    )
    (net (code "36") (name "Net-(CHG-PROG)") (class "Default")
      (node (ref "CHG") (pin "5") (pinfunction "PROG_5") (pintype "input"))
      (node (ref "R21") (pin "1") (pinfunction "1_1") (pintype "passive"))
    )
    (net (code "37") (name "Net-(CHG-STAT)") (class "Default")
      (node (ref "CHG") (pin "1") (pinfunction "STAT_1") (pintype "output"))
      (node (ref "R20") (pin "2") (pinfunction "2_2") (pintype "passive"))
    )
    (net (code "38") (name "Net-(LED1-PadC)") (class "Default")
      (node (ref "LED1") (pin "C") (pinfunction "C_C") (pintype "passive"))
      (node (ref "R20") (pin "1") (pinfunction "1_1") (pintype "passive"))
    )
    (net (code "39") (name "Net-(LED2-PadA)") (class "Default")
      (node (ref "LED2") (pin "A") (pinfunction "A_A") (pintype "passive"))
      (node (ref "R22") (pin "1") (pinfunction "1_1") (pintype "passive"))
    )
    (net (code "40") (name "Net-(LED3-PadP$2)") (class "Default")
      (node (ref "LED3") (pin "P$2") (pinfunction "P$2_P$2") (pintype "passive"))
      (node (ref "R23") (pin "1") (pinfunction "1_1") (pintype "passive"))
    )
    (net (code "41") (name "Net-(LED3-PadP$3)") (class "Default")
      (node (ref "LED3") (pin "P$3") (pinfunction "P$3_P$3") (pintype "passive"))
      (node (ref "R24") (pin "1") (pinfunction "1_1") (pintype "passive"))
    )
    (net (code "42") (name "Net-(LED3-PadP$4)") (class "Default")
      (node (ref "LED3") (pin "P$4") (pinfunction "P$4_P$4") (pintype "passive"))
      (node (ref "R25") (pin "1") (pinfunction "1_1") (pintype "passive"))
    )
    (net (code "43") (name "Net-(R22-Pad2)") (class "Default")
      (node (ref "R22") (pin "2") (pinfunction "2_2") (pintype "passive"))
      (node (ref "SLIDE_ON") (pin "P") (pinfunction "P_P") (pintype "passive"))
    )
    (net (code "44") (name "Net-(U1-XTALIN)") (class "Default")
      (node (ref "C7") (pin "1") (pinfunction "1_1") (pintype "passive"))
      (node (ref "R14") (pin "2") (pinfunction "2_2") (pintype "passive"))
      (node (ref "U1") (pin "18") (pinfunction "XTALIN_18") (pintype "input"))
      (node (ref "Y1") (pin "2") (pinfunction "2_2") (pintype "passive"))
    )
    (net (code "45") (name "Net-(U1-XTALOUT)") (class "Default")
      (node (ref "C6") (pin "1") (pinfunction "1_1") (pintype "passive"))
      (node (ref "R14") (pin "1") (pinfunction "1_1") (pintype "passive"))
      (node (ref "U1") (pin "17") (pinfunction "XTALOUT_17") (pintype "output"))
      (node (ref "Y1") (pin "1") (pinfunction "1_1") (pintype "passive"))
    )
    (net (code "46") (name "OUT") (class "Default")
      (node (ref "C19") (pin "C") (pinfunction "-_C") (pintype "passive"))
      (node (ref "J1") (pin "4") (pinfunction "4_4") (pintype "passive"))
    )
    (net (code "47") (name "PVIN") (class "Default")
      (node (ref "C13") (pin "1") (pinfunction "1_1") (pintype "passive"))
      (node (ref "CHG") (pin "4") (pinfunction "VIN_4") (pintype "power_in"))
      (node (ref "D2") (pin "C") (pinfunction "C_C") (pintype "passive"))
      (node (ref "LED1") (pin "A") (pinfunction "A_A") (pintype "passive"))
      (node (ref "U$1") (pin "1") (pinfunction "VIN_1") (pintype "power_in"))
    )
    (net (code "48") (name "RIGHT") (class "Default")
      (node (ref "R6") (pin "2") (pinfunction "2_2") (pintype "passive"))
      (node (ref "R8") (pin "1") (pinfunction "1_1") (pintype "passive"))
      (node (ref "U1") (pin "39") (pinfunction "RIGHT_39") (pintype "bidirectional"))
    )
    (net (code "49") (name "RST_3V") (class "Default")
      (node (ref "C5") (pin "1") (pinfunction "1_1") (pintype "passive"))
      (node (ref "R10") (pin "2") (pinfunction "2_2") (pintype "passive"))
      (node (ref "R11") (pin "2") (pinfunction "2_2") (pintype "passive"))
      (node (ref "U$1") (pin "19") (pinfunction "D6_19") (pintype "bidirectional"))
      (node (ref "U1") (pin "3") (pinfunction "XRESET_3") (pintype "bidirectional"))
    )
    (net (code "50") (name "RX") (class "Default")
      (node (ref "J2") (pin "2") (pinfunction "2_2") (pintype "passive"))
      (node (ref "U$1") (pin "4") (pinfunction "RX_4") (pintype "bidirectional"))
    )
    (net (code "51") (name "RX_VS1053") (class "Default")
      (node (ref "R13") (pin "2") (pinfunction "2_2") (pintype "passive"))
      (node (ref "U1") (pin "26") (pinfunction "RX_26") (pintype "bidirectional"))
    )
    (net (code "52") (name "R_OUT") (class "Default")
      (node (ref "AUXCONN") (pin "3") (pinfunction "3_3") (pintype "passive"))
      (node (ref "C1") (pin "-") (pinfunction "-_-") (pintype "passive"))
    )
    (net (code "53") (name "SCLK_3V") (class "Default")
      (node (ref "CN1") (pin "5") (pinfunction "SCLK_5") (pintype "input"))
      (node (ref "U$1") (pin "9") (pinfunction "A3_9") (pintype "bidirectional"))
      (node (ref "U1") (pin "28") (pinfunction "SCLK_28") (pintype "bidirectional"))
      (node (ref "U2") (pin "14") (pinfunction "SCL_14") (pintype "bidirectional"))
    )
    (net (code "54") (name "SDCS_3V") (class "Default")
      (node (ref "CN1") (pin "2") (pinfunction "CS_2") (pintype "input"))
      (node (ref "R19") (pin "2") (pinfunction "2_2") (pintype "passive"))
      (node (ref "U$1") (pin "16") (pinfunction "D3_16") (pintype "bidirectional"))
    )
    (net (code "55") (name "SD_DETECT") (class "Default")
      (node (ref "CN1") (pin "CD1") (pinfunction "CARD_DETECT_CD1") (pintype "passive"))
    )
    (net (code "56") (name "SP3DATA") (class "Default")
      (node (ref "SWITCH") (pin "1") (pinfunction "1_1") (pintype "bidirectional"))
      (node (ref "U$1") (pin "6") (pinfunction "DAC_6") (pintype "bidirectional"))
    )
    (net (code "57") (name "SP3PLAY") (class "Default")
      (node (ref "SWITCH") (pin "2") (pinfunction "2_2") (pintype "bidirectional"))
      (node (ref "U$1") (pin "20") (pinfunction "D7_20") (pintype "bidirectional"))
    )
    (net (code "58") (name "SP3REC") (class "Default")
      (node (ref "SWITCH") (pin "4") (pinfunction "4_4") (pintype "bidirectional"))
      (node (ref "U$1") (pin "17") (pinfunction "D4_17") (pintype "bidirectional"))
    )
    (net (code "59") (name "TX") (class "Default")
      (node (ref "J2") (pin "3") (pinfunction "3_3") (pintype "passive"))
      (node (ref "U$1") (pin "3") (pinfunction "TX_3") (pintype "bidirectional"))
    )
    (net (code "60") (name "VBAT") (class "Default")
      (node (ref "U$1") (pin "22") (pinfunction "VBAT_22") (pintype "power_in"))
    )
    (net (code "61") (name "XDCS_3V") (class "Default")
      (node (ref "R12") (pin "2") (pinfunction "2_2") (pintype "passive"))
      (node (ref "U$1") (pin "18") (pinfunction "D5_18") (pintype "bidirectional"))
      (node (ref "U1") (pin "13") (pinfunction "XDCS/BSYNC_13") (pintype "bidirectional"))
    )
    (net (code "62") (name "unconnected-(CN1-CARD_DETECT1-PadCD2)") (class "Default")
      (node (ref "CN1") (pin "CD2") (pinfunction "CARD_DETECT1_CD2") (pintype "passive"))
    )
    (net (code "63") (name "unconnected-(CN1-DAT1-Pad8)") (class "Default")
      (node (ref "CN1") (pin "8") (pinfunction "DAT1_8") (pintype "bidirectional"))
    )
    (net (code "64") (name "unconnected-(CN1-DAT2-Pad1)") (class "Default")
      (node (ref "CN1") (pin "1") (pinfunction "DAT2_1") (pintype "bidirectional"))
    )
    (net (code "65") (name "unconnected-(IC1-NC{slash}ADJ-Pad4)") (class "Default")
      (node (ref "IC1") (pin "4") (pinfunction "NC/ADJ_4") (pintype "bidirectional"))
    )
    (net (code "66") (name "unconnected-(IC1-~{SHUTDOWN}-Pad3)") (class "Default")
      (node (ref "IC1") (pin "3") (pinfunction "~{SHUTDOWN}_3") (pintype "bidirectional"))
    )
    (net (code "67") (name "unconnected-(U$1A-A1-Pad11)") (class "Default")
      (node (ref "U$1") (pin "11") (pinfunction "A1_11") (pintype "bidirectional"))
    )
    (net (code "68") (name "unconnected-(U$1A-~{RST}-Pad23)") (class "Default")
      (node (ref "U$1") (pin "23") (pinfunction "~{RST}_23") (pintype "bidirectional"))
    )
    (net (code "69") (name "unconnected-(U$1B-EN-Pad25)") (class "Default")
      (node (ref "U$1") (pin "25") (pinfunction "EN_25") (pintype "bidirectional"))
    )
    (net (code "70") (name "unconnected-(U$1B-RGB_BLUE-Pad29)") (class "Default")
      (node (ref "U$1") (pin "29") (pinfunction "RGB_BLUE_29") (pintype "bidirectional"))
    )
    (net (code "71") (name "unconnected-(U$1B-RGB_GREEN-Pad28)") (class "Default")
      (node (ref "U$1") (pin "28") (pinfunction "RGB_GREEN_28") (pintype "bidirectional"))
    )
    (net (code "72") (name "unconnected-(U$1B-RGB_RED-Pad27)") (class "Default")
      (node (ref "U$1") (pin "27") (pinfunction "RGB_RED_27") (pintype "bidirectional"))
    )
    (net (code "73") (name "unconnected-(U$1B-USB_D+-Pad31)") (class "Default")
      (node (ref "U$1") (pin "31") (pinfunction "USB_D+_31") (pintype "bidirectional"))
    )
    (net (code "74") (name "unconnected-(U$1B-USB_D--Pad30)") (class "Default")
      (node (ref "U$1") (pin "30") (pinfunction "USB_D-_30") (pintype "bidirectional"))
    )
    (net (code "75") (name "unconnected-(U$1B-~{SETUP}-Pad26)") (class "Default")
      (node (ref "U$1") (pin "26") (pinfunction "~{SETUP}_26") (pintype "bidirectional"))
    )
    (net (code "76") (name "unconnected-(U1-GBUF-Pad42)") (class "Default")
      (node (ref "U1") (pin "42") (pinfunction "GBUF_42") (pintype "bidirectional"))
    )
    (net (code "77") (name "unconnected-(U1-RCAP-Pad44)") (class "Default")
      (node (ref "U1") (pin "44") (pinfunction "RCAP_44") (pintype "bidirectional"))
    )
    (net (code "78") (name "unconnected-(U1-TX-Pad27)") (class "Default")
      (node (ref "U1") (pin "27") (pinfunction "TX_27") (pintype "bidirectional"))
    )
    (net (code "79") (name "unconnected-(U2-INT1-Pad8)") (class "Default")
      (node (ref "U2") (pin "8") (pinfunction "INT1_8") (pintype "bidirectional"))
    )
    (net (code "80") (name "unconnected-(U2-INT2-Pad9)") (class "Default")
      (node (ref "U2") (pin "9") (pinfunction "INT2_9") (pintype "bidirectional"))
    )
    (net (code "81") (name "unconnected-(U2-NC-Pad3)") (class "Default")
      (node (ref "U2") (pin "3") (pinfunction "NC_3") (pintype "bidirectional"))
    )
    (net (code "82") (name "unconnected-(U2-NC-Pad10)") (class "Default")
      (node (ref "U2") (pin "10") (pinfunction "NC_10") (pintype "bidirectional"))
    )
    (net (code "83") (name "unconnected-(U2-NC-Pad11)") (class "Default")
      (node (ref "U2") (pin "11") (pinfunction "NC_11") (pintype "bidirectional"))
    )
  )
)
